# bluz_remote_v1.net
KiCad netlist of a schematic drawn in EAGLE
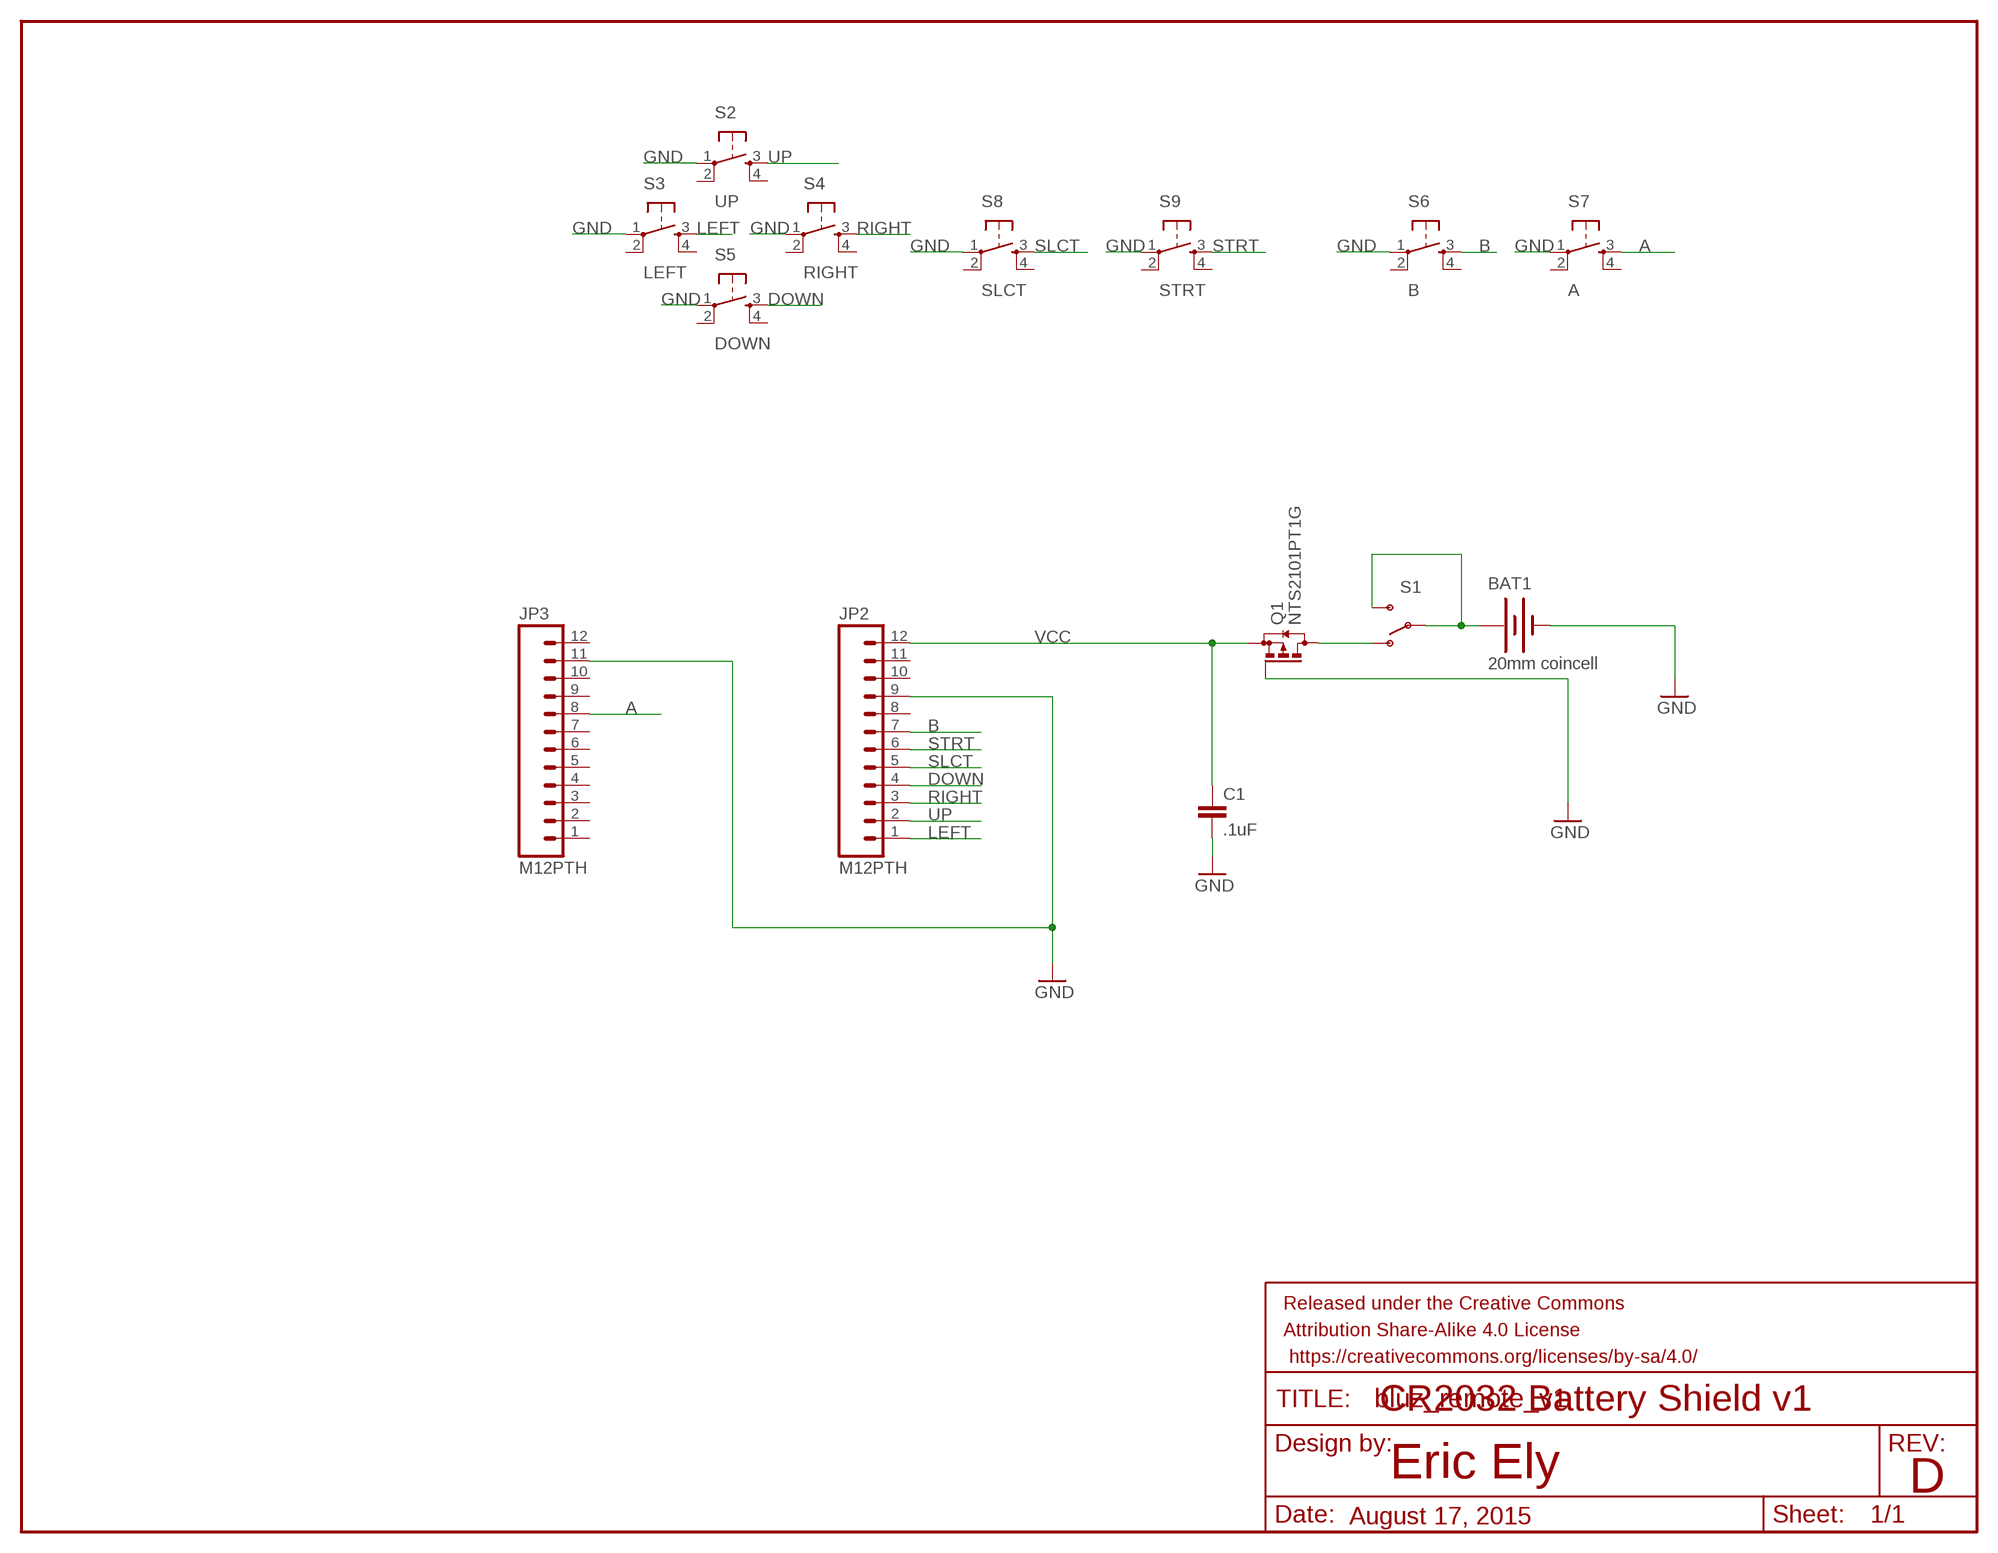
[diagram p0: schematic, sheet 1]

(export (version "E")
  (design (tool "Eeschema 10.0.6"))
  (components
    (comp (ref "BAT1")
      (value "20mm coincell")
      (footprint "eagle-import:BATTCON_20MM_4LEGS")
      (libsource (lib "eagle-import") (part "BATTERY20MM_4LEGS"))
    )
    (comp (ref "C1")
      (value ".1uF")
      (footprint "eagle-import:0603-CAP")
      (libsource (lib "eagle-import") (part "CAP0603-CAP"))
    )
    (comp (ref "FRAME1")
      (value "FRAME-LETTER")
      (footprint "eagle-import:CREATIVE_COMMONS")
      (libsource (lib "eagle-import") (part "FRAME-LETTER"))
    )
    (comp (ref "JP2")
      (value "M12PTH")
      (footprint "eagle-import:1X12")
      (libsource (lib "eagle-import") (part "M12PTH"))
    )
    (comp (ref "JP3")
      (value "M12PTH")
      (footprint "eagle-import:1X12")
      (libsource (lib "eagle-import") (part "M12PTH"))
    )
    (comp (ref "Q1")
      (value "NTS2101PT1G")
      (footprint "eagle-import:SOT323")
      (libsource (lib "eagle-import") (part "NTS2101PT1G"))
    )
    (comp (ref "S1")
      (value "SWITCH-SPDTKIT")
      (footprint "eagle-import:SWITCH-SPDT_KIT")
      (libsource (lib "eagle-import") (part "SWITCH-SPDTKIT"))
    )
    (comp (ref "S2")
      (value "UP")
      (footprint "eagle-import:TACTILE_SWITCH_SMD")
      (libsource (lib "eagle-import") (part "TAC_SWITCHSMD"))
    )
    (comp (ref "S3")
      (value "LEFT")
      (footprint "eagle-import:TACTILE_SWITCH_SMD")
      (libsource (lib "eagle-import") (part "TAC_SWITCHSMD"))
    )
    (comp (ref "S4")
      (value "RIGHT")
      (footprint "eagle-import:TACTILE_SWITCH_SMD")
      (libsource (lib "eagle-import") (part "TAC_SWITCHSMD"))
    )
    (comp (ref "S5")
      (value "DOWN")
      (footprint "eagle-import:TACTILE_SWITCH_SMD")
      (libsource (lib "eagle-import") (part "TAC_SWITCHSMD"))
    )
    (comp (ref "S6")
      (value "B")
      (footprint "eagle-import:TACTILE_SWITCH_SMD")
      (libsource (lib "eagle-import") (part "TAC_SWITCHSMD"))
    )
    (comp (ref "S7")
      (value "A")
      (footprint "eagle-import:TACTILE_SWITCH_SMD")
      (libsource (lib "eagle-import") (part "TAC_SWITCHSMD"))
    )
    (comp (ref "S8")
      (value "SLCT")
      (footprint "eagle-import:TACTILE_SWITCH_SMD")
      (libsource (lib "eagle-import") (part "TAC_SWITCHSMD"))
    )
    (comp (ref "S9")
      (value "STRT")
      (footprint "eagle-import:TACTILE_SWITCH_SMD")
      (libsource (lib "eagle-import") (part "TAC_SWITCHSMD"))
    )
  )
  (nets
    (net (code "1") (name "/A") (class "Default")
      (node (ref "JP3") (pin "8") (pinfunction "8_8") (pintype "passive"))
      (node (ref "S7") (pin "3") (pinfunction "3_3") (pintype "passive"))
    )
    (net (code "2") (name "/B") (class "Default")
      (node (ref "JP2") (pin "7") (pinfunction "7_7") (pintype "passive"))
      (node (ref "S6") (pin "3") (pinfunction "3_3") (pintype "passive"))
    )
    (net (code "3") (name "/DOWN") (class "Default")
      (node (ref "JP2") (pin "4") (pinfunction "4_4") (pintype "passive"))
      (node (ref "S5") (pin "3") (pinfunction "3_3") (pintype "passive"))
    )
    (net (code "4") (name "/LEFT") (class "Default")
      (node (ref "JP2") (pin "1") (pinfunction "1_1") (pintype "passive"))
      (node (ref "S3") (pin "3") (pinfunction "3_3") (pintype "passive"))
    )
    (net (code "5") (name "/RIGHT") (class "Default")
      (node (ref "JP2") (pin "3") (pinfunction "3_3") (pintype "passive"))
      (node (ref "S4") (pin "3") (pinfunction "3_3") (pintype "passive"))
    )
    (net (code "6") (name "/SLCT") (class "Default")
      (node (ref "JP2") (pin "5") (pinfunction "5_5") (pintype "passive"))
      (node (ref "S8") (pin "3") (pinfunction "3_3") (pintype "passive"))
    )
    (net (code "7") (name "/STRT") (class "Default")
      (node (ref "JP2") (pin "6") (pinfunction "6_6") (pintype "passive"))
      (node (ref "S9") (pin "3") (pinfunction "3_3") (pintype "passive"))
    )
    (net (code "8") (name "/UP") (class "Default")
      (node (ref "JP2") (pin "2") (pinfunction "2_2") (pintype "passive"))
      (node (ref "S2") (pin "3") (pinfunction "3_3") (pintype "passive"))
    )
    (net (code "9") (name "/VCC") (class "Default")
      (node (ref "C1") (pin "1") (pinfunction "1_1") (pintype "passive"))
      (node (ref "JP2") (pin "12") (pinfunction "12_12") (pintype "passive"))
      (node (ref "Q1") (pin "2") (pinfunction "S_2") (pintype "passive"))
    )
    (net (code "10") (name "GND") (class "Default")
      (node (ref "BAT1") (pin "2") (pinfunction "-_2") (pintype "power_in"))
      (node (ref "C1") (pin "2") (pinfunction "2_2") (pintype "passive"))
      (node (ref "JP2") (pin "9") (pinfunction "9_9") (pintype "passive"))
      (node (ref "JP3") (pin "11") (pinfunction "11_11") (pintype "passive"))
      (node (ref "Q1") (pin "1") (pinfunction "G_1") (pintype "passive"))
      (node (ref "S2") (pin "1") (pinfunction "1_1") (pintype "passive"))
      (node (ref "S3") (pin "1") (pinfunction "1_1") (pintype "passive"))
      (node (ref "S4") (pin "1") (pinfunction "1_1") (pintype "passive"))
      (node (ref "S5") (pin "1") (pinfunction "1_1") (pintype "passive"))
      (node (ref "S6") (pin "1") (pinfunction "1_1") (pintype "passive"))
      (node (ref "S7") (pin "1") (pinfunction "1_1") (pintype "passive"))
      (node (ref "S8") (pin "1") (pinfunction "1_1") (pintype "passive"))
      (node (ref "S9") (pin "1") (pinfunction "1_1") (pintype "passive"))
    )
    (net (code "11") (name "Net-(BAT1-+)") (class "Default")
      (node (ref "BAT1") (pin "1") (pinfunction "+_1") (pintype "power_in"))
      (node (ref "S1") (pin "2") (pinfunction "P_2") (pintype "passive"))
      (node (ref "S1") (pin "3") (pinfunction "S_3") (pintype "passive"))
    )
    (net (code "12") (name "Net-(Q1-D)") (class "Default")
      (node (ref "Q1") (pin "3") (pinfunction "D_3") (pintype "passive"))
      (node (ref "S1") (pin "1") (pinfunction "O_1") (pintype "passive"))
    )
    (net (code "13") (name "unconnected-(JP2-Pad8)") (class "Default")
      (node (ref "JP2") (pin "8") (pinfunction "8_8") (pintype "passive"))
    )
    (net (code "14") (name "unconnected-(JP2-Pad10)") (class "Default")
      (node (ref "JP2") (pin "10") (pinfunction "10_10") (pintype "passive"))
    )
    (net (code "15") (name "unconnected-(JP2-Pad11)") (class "Default")
      (node (ref "JP2") (pin "11") (pinfunction "11_11") (pintype "passive"))
    )
    (net (code "16") (name "unconnected-(JP3-Pad1)") (class "Default")
      (node (ref "JP3") (pin "1") (pinfunction "1_1") (pintype "passive"))
    )
    (net (code "17") (name "unconnected-(JP3-Pad2)") (class "Default")
      (node (ref "JP3") (pin "2") (pinfunction "2_2") (pintype "passive"))
    )
    (net (code "18") (name "unconnected-(JP3-Pad3)") (class "Default")
      (node (ref "JP3") (pin "3") (pinfunction "3_3") (pintype "passive"))
    )
    (net (code "19") (name "unconnected-(JP3-Pad4)") (class "Default")
      (node (ref "JP3") (pin "4") (pinfunction "4_4") (pintype "passive"))
    )
    (net (code "20") (name "unconnected-(JP3-Pad5)") (class "Default")
      (node (ref "JP3") (pin "5") (pinfunction "5_5") (pintype "passive"))
    )
    (net (code "21") (name "unconnected-(JP3-Pad6)") (class "Default")
      (node (ref "JP3") (pin "6") (pinfunction "6_6") (pintype "passive"))
    )
    (net (code "22") (name "unconnected-(JP3-Pad7)") (class "Default")
      (node (ref "JP3") (pin "7") (pinfunction "7_7") (pintype "passive"))
    )
    (net (code "23") (name "unconnected-(JP3-Pad9)") (class "Default")
      (node (ref "JP3") (pin "9") (pinfunction "9_9") (pintype "passive"))
    )
    (net (code "24") (name "unconnected-(JP3-Pad10)") (class "Default")
      (node (ref "JP3") (pin "10") (pinfunction "10_10") (pintype "passive"))
    )
    (net (code "25") (name "unconnected-(JP3-Pad12)") (class "Default")
      (node (ref "JP3") (pin "12") (pinfunction "12_12") (pintype "passive"))
    )
    (net (code "26") (name "unconnected-(S2-Pad2)") (class "Default")
      (node (ref "S2") (pin "2") (pinfunction "2_2") (pintype "passive"))
    )
    (net (code "27") (name "unconnected-(S2-Pad4)") (class "Default")
      (node (ref "S2") (pin "4") (pinfunction "4_4") (pintype "passive"))
    )
    (net (code "28") (name "unconnected-(S3-Pad2)") (class "Default")
      (node (ref "S3") (pin "2") (pinfunction "2_2") (pintype "passive"))
    )
    (net (code "29") (name "unconnected-(S3-Pad4)") (class "Default")
      (node (ref "S3") (pin "4") (pinfunction "4_4") (pintype "passive"))
    )
    (net (code "30") (name "unconnected-(S4-Pad2)") (class "Default")
      (node (ref "S4") (pin "2") (pinfunction "2_2") (pintype "passive"))
    )
    (net (code "31") (name "unconnected-(S4-Pad4)") (class "Default")
      (node (ref "S4") (pin "4") (pinfunction "4_4") (pintype "passive"))
    )
    (net (code "32") (name "unconnected-(S5-Pad2)") (class "Default")
      (node (ref "S5") (pin "2") (pinfunction "2_2") (pintype "passive"))
    )
    (net (code "33") (name "unconnected-(S5-Pad4)") (class "Default")
      (node (ref "S5") (pin "4") (pinfunction "4_4") (pintype "passive"))
    )
    (net (code "34") (name "unconnected-(S6-Pad2)") (class "Default")
      (node (ref "S6") (pin "2") (pinfunction "2_2") (pintype "passive"))
    )
    (net (code "35") (name "unconnected-(S6-Pad4)") (class "Default")
      (node (ref "S6") (pin "4") (pinfunction "4_4") (pintype "passive"))
    )
    (net (code "36") (name "unconnected-(S7-Pad2)") (class "Default")
      (node (ref "S7") (pin "2") (pinfunction "2_2") (pintype "passive"))
    )
    (net (code "37") (name "unconnected-(S7-Pad4)") (class "Default")
      (node (ref "S7") (pin "4") (pinfunction "4_4") (pintype "passive"))
    )
    (net (code "38") (name "unconnected-(S8-Pad2)") (class "Default")
      (node (ref "S8") (pin "2") (pinfunction "2_2") (pintype "passive"))
    )
    (net (code "39") (name "unconnected-(S8-Pad4)") (class "Default")
      (node (ref "S8") (pin "4") (pinfunction "4_4") (pintype "passive"))
    )
    (net (code "40") (name "unconnected-(S9-Pad2)") (class "Default")
      (node (ref "S9") (pin "2") (pinfunction "2_2") (pintype "passive"))
    )
    (net (code "41") (name "unconnected-(S9-Pad4)") (class "Default")
      (node (ref "S9") (pin "4") (pinfunction "4_4") (pintype "passive"))
    )
  )
)
